# Peripherals.net
KiCad netlist of a schematic drawn in Altium Designer
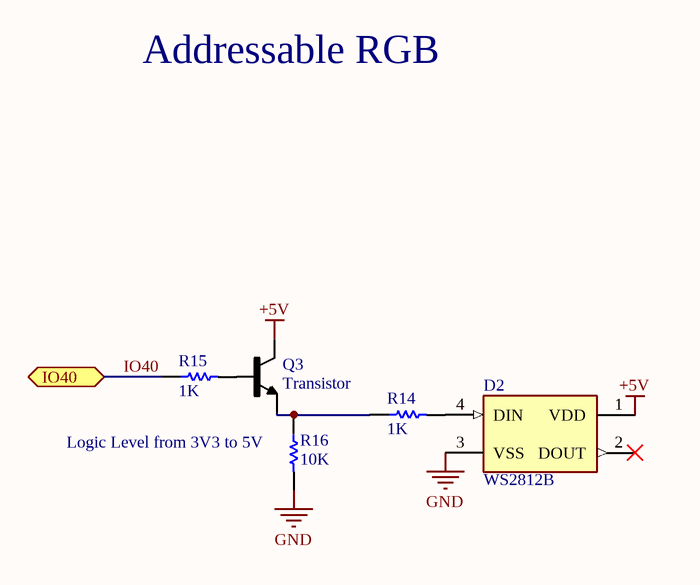
[diagram p0: Peripherals.SchDoc]

(export (version "E")
  (design (tool "Eeschema 10.0.6"))
  (components
    (comp (ref "D2")
      (value "WS2812B")
      (footprint "WS28128B")
      (description "Intelligent control LED integrated light source")
      (libsource (lib "Schlib1") (part "WS2812B"))
    )
    (comp (ref "Q3")
      (value "Transistor")
      (footprint "Transistor")
      (libsource (lib "Schlib1") (part "Transistor"))
    )
    (comp (ref "R14") (value "1K") (footprint "R0402") (libsource (lib "Schlib1") (part "Res")))
    (comp (ref "R15") (value "1K") (footprint "R0402") (libsource (lib "Schlib1") (part "Res")))
    (comp (ref "R16") (value "10K") (footprint "R0402") (libsource (lib "Schlib1") (part "Res")))
  )
  (nets
    (net (code "1") (name "+5V") (class "Default")
      (node (ref "D2") (pin "1") (pinfunction "VDD_1") (pintype "power_in"))
      (node (ref "Q3") (pin "3") (pinfunction "C_3") (pintype "passive"))
    )
    (net (code "2") (name "/IO40") (class "Default")
      (node (ref "R15") (pin "02") (pinfunction "02_02") (pintype "passive"))
    )
    (net (code "3") (name "GND") (class "Default")
      (node (ref "D2") (pin "3") (pinfunction "VSS_3") (pintype "power_in"))
      (node (ref "R16") (pin "01") (pinfunction "01_01") (pintype "passive"))
    )
    (net (code "4") (name "Net-(D2-DIN)") (class "Default")
      (node (ref "D2") (pin "4") (pinfunction "DIN_4") (pintype "input"))
      (node (ref "R14") (pin "01") (pinfunction "01_01") (pintype "passive"))
    )
    (net (code "5") (name "Net-(Q3-B)") (class "Default")
      (node (ref "Q3") (pin "1") (pinfunction "B_1") (pintype "passive"))
      (node (ref "R15") (pin "01") (pinfunction "01_01") (pintype "passive"))
    )
    (net (code "6") (name "Net-(Q3-E)") (class "Default")
      (node (ref "Q3") (pin "2") (pinfunction "E_2") (pintype "passive"))
      (node (ref "R14") (pin "02") (pinfunction "02_02") (pintype "passive"))
      (node (ref "R16") (pin "02") (pinfunction "02_02") (pintype "passive"))
    )
    (net (code "7") (name "unconnected-(D2-DOUT-Pad2)") (class "Default")
      (node (ref "D2") (pin "2") (pinfunction "DOUT_2") (pintype "output+no_connect"))
    )
  )
)
